# FS-01.net
KiCad netlist of a schematic drawn in Altium Designer
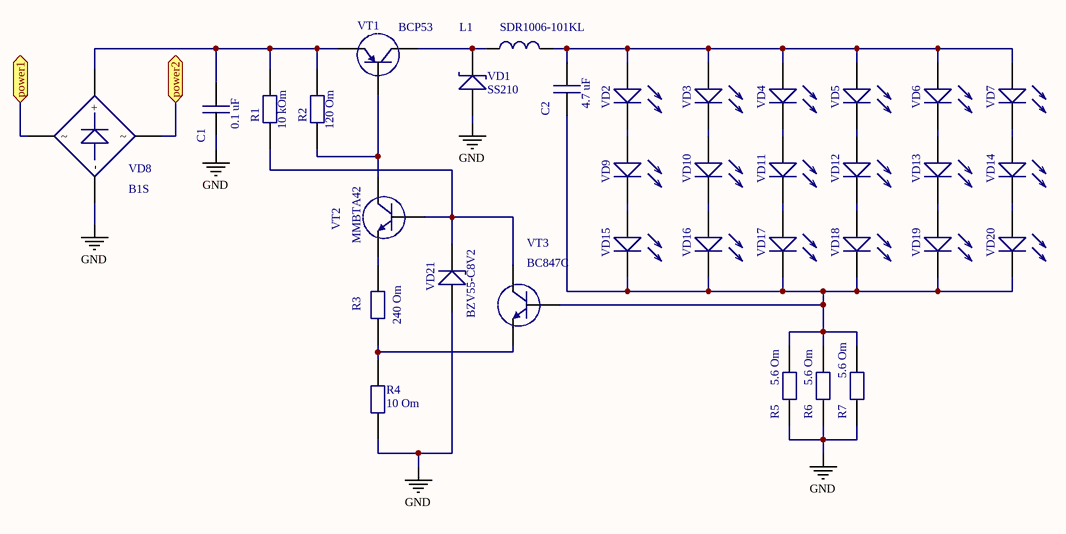
[diagram p0: FS-01.SchDoc]

(export (version "E")
  (design (tool "Eeschema 10.0.6"))
  (components
    (comp (ref "C1")
      (value "0.1 uF")
      (footprint "CAP1206")
      (fields (field (name "Comment") "Capacitor"))
      (libsource (lib "my_library") (part "Capacitor"))
    )
    (comp (ref "C2")
      (value "4.7 uF")
      (footprint "CAP1206")
      (fields (field (name "Comment") "Capacitor"))
      (libsource (lib "my_library") (part "Capacitor"))
    )
    (comp (ref "L1")
      (value "SDR1006-101KL")
      (footprint "SDR1006")
      (fields (field (name "Comment") "coil"))
      (libsource (lib "my_library") (part "coil"))
    )
    (comp (ref "R1")
      (value "10 kOm")
      (footprint "RES1206")
      (fields (field (name "Comment") "Resistor"))
      (libsource (lib "my_library") (part "Resistor"))
    )
    (comp (ref "R2")
      (value "120 Om")
      (footprint "RES1206")
      (fields (field (name "Comment") "Resistor"))
      (libsource (lib "my_library") (part "Resistor"))
    )
    (comp (ref "R3")
      (value "240 Om")
      (footprint "RES1206")
      (fields (field (name "Comment") "Resistor"))
      (libsource (lib "my_library") (part "Resistor"))
    )
    (comp (ref "R4")
      (value "10 Om")
      (footprint "RES1206")
      (fields (field (name "Comment") "Resistor"))
      (libsource (lib "my_library") (part "Resistor"))
    )
    (comp (ref "R5")
      (value "5.6 Om")
      (footprint "RES1206")
      (fields (field (name "Comment") "Resistor"))
      (libsource (lib "my_library") (part "Resistor"))
    )
    (comp (ref "R6")
      (value "5.6 Om")
      (footprint "RES1206")
      (fields (field (name "Comment") "Resistor"))
      (libsource (lib "my_library") (part "Resistor"))
    )
    (comp (ref "R7")
      (value "5.6 Om")
      (footprint "RES1206")
      (fields (field (name "Comment") "Resistor"))
      (libsource (lib "my_library") (part "Resistor"))
    )
    (comp (ref "VD1")
      (value "SS210")
      (footprint "SMB1")
      (fields (field (name "Comment") "Schottky"))
      (libsource (lib "my_library") (part "Schottky"))
    )
    (comp (ref "VD2") (value "LED") (footprint "LED_SAKURA") (libsource (lib "FOS-00 Rev 1_4") (part "LED")))
    (comp (ref "VD3") (value "LED") (footprint "LED_SAKURA") (libsource (lib "FOS-00 Rev 1_4") (part "LED")))
    (comp (ref "VD4") (value "LED") (footprint "LED_SAKURA") (libsource (lib "FOS-00 Rev 1_4") (part "LED")))
    (comp (ref "VD5") (value "LED") (footprint "LED_SAKURA") (libsource (lib "FOS-00 Rev 1_4") (part "LED")))
    (comp (ref "VD6") (value "LED") (footprint "LED_SAKURA") (libsource (lib "FOS-00 Rev 1_4") (part "LED")))
    (comp (ref "VD7") (value "LED") (footprint "LED_SAKURA") (libsource (lib "FOS-00 Rev 1_4") (part "LED")))
    (comp (ref "VD8")
      (value "B1S")
      (footprint "db-1ms")
      (fields (field (name "Comment") "Diode Bridge"))
      (libsource (lib "FOS-00 Rev 1_4") (part "Diode Bridge"))
    )
    (comp (ref "VD9") (value "LED") (footprint "LED_SAKURA") (libsource (lib "FOS-00 Rev 1_4") (part "LED")))
    (comp (ref "VD10") (value "LED") (footprint "LED_SAKURA") (libsource (lib "FOS-00 Rev 1_4") (part "LED")))
    (comp (ref "VD11") (value "LED") (footprint "LED_SAKURA") (libsource (lib "FOS-00 Rev 1_4") (part "LED")))
    (comp (ref "VD12") (value "LED") (footprint "LED_SAKURA") (libsource (lib "FOS-00 Rev 1_4") (part "LED")))
    (comp (ref "VD13") (value "LED") (footprint "LED_SAKURA") (libsource (lib "FOS-00 Rev 1_4") (part "LED")))
    (comp (ref "VD14") (value "LED") (footprint "LED_SAKURA") (libsource (lib "FOS-00 Rev 1_4") (part "LED")))
    (comp (ref "VD15") (value "LED") (footprint "LED_SAKURA") (libsource (lib "FOS-00 Rev 1_4") (part "LED")))
    (comp (ref "VD16") (value "LED") (footprint "LED_SAKURA") (libsource (lib "FOS-00 Rev 1_4") (part "LED")))
    (comp (ref "VD17") (value "LED") (footprint "LED_SAKURA") (libsource (lib "FOS-00 Rev 1_4") (part "LED")))
    (comp (ref "VD18") (value "LED") (footprint "LED_SAKURA") (libsource (lib "FOS-00 Rev 1_4") (part "LED")))
    (comp (ref "VD19") (value "LED") (footprint "LED_SAKURA") (libsource (lib "FOS-00 Rev 1_4") (part "LED")))
    (comp (ref "VD20") (value "LED") (footprint "LED_SAKURA") (libsource (lib "FOS-00 Rev 1_4") (part "LED")))
    (comp (ref "VD21")
      (value "BZV55-C8V2")
      (footprint "minimelf")
      (fields (field (name "Comment") "Zenner"))
      (libsource (lib "my_library") (part "Zenner"))
    )
    (comp (ref "VT1")
      (value "BCP53")
      (footprint "SOT223")
      (fields (field (name "Comment") "PNP"))
      (libsource (lib "my_library") (part "PNP"))
    )
    (comp (ref "VT2")
      (value "MMBTA42")
      (footprint "SOT 23")
      (fields (field (name "Comment") "NPN"))
      (libsource (lib "my_library") (part "NPN"))
    )
    (comp (ref "VT3")
      (value "BC847C")
      (footprint "SOT 23")
      (fields (field (name "Comment") "NPN"))
      (libsource (lib "my_library") (part "NPN"))
    )
  )
  (nets
    (net (code "1") (name "/power1") (class "Default")
      (node (ref "VD8") (pin "3") (pinfunction "~_3") (pintype "passive"))
    )
    (net (code "2") (name "/power2") (class "Default")
      (node (ref "VD8") (pin "4") (pinfunction "~_4") (pintype "passive"))
    )
    (net (code "3") (name "GND") (class "Default")
      (node (ref "C1") (pin "1") (pinfunction "1_1") (pintype "passive"))
      (node (ref "R4") (pin "1") (pinfunction "1_1") (pintype "passive"))
      (node (ref "R5") (pin "1") (pinfunction "1_1") (pintype "passive"))
      (node (ref "R6") (pin "1") (pinfunction "1_1") (pintype "passive"))
      (node (ref "R7") (pin "1") (pinfunction "1_1") (pintype "passive"))
      (node (ref "VD1") (pin "2") (pinfunction "2_2") (pintype "passive"))
      (node (ref "VD21") (pin "2") (pinfunction "2_2") (pintype "passive"))
      (node (ref "VD8") (pin "2") (pinfunction "-_2") (pintype "passive"))
    )
    (net (code "4") (name "Net-(C2-Pad1)") (class "Default")
      (node (ref "C2") (pin "1") (pinfunction "1_1") (pintype "passive"))
      (node (ref "R5") (pin "2") (pinfunction "2_2") (pintype "passive"))
      (node (ref "R6") (pin "2") (pinfunction "2_2") (pintype "passive"))
      (node (ref "R7") (pin "2") (pinfunction "2_2") (pintype "passive"))
      (node (ref "VD15") (pin "1") (pinfunction "1_1") (pintype "passive"))
      (node (ref "VD16") (pin "1") (pinfunction "1_1") (pintype "passive"))
      (node (ref "VD17") (pin "1") (pinfunction "1_1") (pintype "passive"))
      (node (ref "VD18") (pin "1") (pinfunction "1_1") (pintype "passive"))
      (node (ref "VD19") (pin "1") (pinfunction "1_1") (pintype "passive"))
      (node (ref "VD20") (pin "1") (pinfunction "1_1") (pintype "passive"))
      (node (ref "VT3") (pin "B") (pinfunction "B_B") (pintype "passive"))
    )
    (net (code "5") (name "Net-(C2-Pad2)") (class "Default")
      (node (ref "C2") (pin "2") (pinfunction "2_2") (pintype "passive"))
      (node (ref "L1") (pin "2") (pinfunction "2_2") (pintype "passive"))
      (node (ref "VD2") (pin "2") (pinfunction "2_2") (pintype "passive"))
      (node (ref "VD3") (pin "2") (pinfunction "2_2") (pintype "passive"))
      (node (ref "VD4") (pin "2") (pinfunction "2_2") (pintype "passive"))
      (node (ref "VD5") (pin "2") (pinfunction "2_2") (pintype "passive"))
      (node (ref "VD6") (pin "2") (pinfunction "2_2") (pintype "passive"))
      (node (ref "VD7") (pin "2") (pinfunction "2_2") (pintype "passive"))
    )
    (net (code "6") (name "Net-(L1-Pad1)") (class "Default")
      (node (ref "L1") (pin "1") (pinfunction "1_1") (pintype "passive"))
      (node (ref "VD1") (pin "1") (pinfunction "1_1") (pintype "passive"))
      (node (ref "VT1") (pin "K") (pinfunction "K_K") (pintype "passive"))
    )
    (net (code "7") (name "Net-(R1-Pad1)") (class "Default")
      (node (ref "R1") (pin "1") (pinfunction "1_1") (pintype "passive"))
      (node (ref "VD21") (pin "1") (pinfunction "1_1") (pintype "passive"))
      (node (ref "VT2") (pin "B") (pinfunction "B_B") (pintype "passive"))
      (node (ref "VT3") (pin "K") (pinfunction "K_K") (pintype "passive"))
    )
    (net (code "8") (name "Net-(R2-Pad2)") (class "Default")
      (node (ref "R2") (pin "2") (pinfunction "2_2") (pintype "passive"))
      (node (ref "VT1") (pin "B") (pinfunction "B_B") (pintype "passive"))
      (node (ref "VT2") (pin "K") (pinfunction "K_K") (pintype "passive"))
    )
    (net (code "9") (name "Net-(R3-Pad1)") (class "Default")
      (node (ref "R3") (pin "1") (pinfunction "1_1") (pintype "passive"))
      (node (ref "R4") (pin "2") (pinfunction "2_2") (pintype "passive"))
      (node (ref "VT3") (pin "E") (pinfunction "E_E") (pintype "passive"))
    )
    (net (code "10") (name "Net-(R3-Pad2)") (class "Default")
      (node (ref "R3") (pin "2") (pinfunction "2_2") (pintype "passive"))
      (node (ref "VT2") (pin "E") (pinfunction "E_E") (pintype "passive"))
    )
    (net (code "11") (name "Net-(VD2-Pad1)") (class "Default")
      (node (ref "VD2") (pin "1") (pinfunction "1_1") (pintype "passive"))
      (node (ref "VD9") (pin "2") (pinfunction "2_2") (pintype "passive"))
    )
    (net (code "12") (name "Net-(VD8-+)") (class "Default")
      (node (ref "C1") (pin "2") (pinfunction "2_2") (pintype "passive"))
      (node (ref "R1") (pin "2") (pinfunction "2_2") (pintype "passive"))
      (node (ref "R2") (pin "1") (pinfunction "1_1") (pintype "passive"))
      (node (ref "VD8") (pin "1") (pinfunction "+_1") (pintype "passive"))
      (node (ref "VT1") (pin "E") (pinfunction "E_E") (pintype "passive"))
    )
    (net (code "13") (name "Net-(VD10-Pad1)") (class "Default")
      (node (ref "VD10") (pin "1") (pinfunction "1_1") (pintype "passive"))
      (node (ref "VD16") (pin "2") (pinfunction "2_2") (pintype "passive"))
    )
    (net (code "14") (name "Net-(VD10-Pad2)") (class "Default")
      (node (ref "VD10") (pin "2") (pinfunction "2_2") (pintype "passive"))
      (node (ref "VD3") (pin "1") (pinfunction "1_1") (pintype "passive"))
    )
    (net (code "15") (name "Net-(VD11-Pad1)") (class "Default")
      (node (ref "VD11") (pin "1") (pinfunction "1_1") (pintype "passive"))
      (node (ref "VD17") (pin "2") (pinfunction "2_2") (pintype "passive"))
    )
    (net (code "16") (name "Net-(VD11-Pad2)") (class "Default")
      (node (ref "VD11") (pin "2") (pinfunction "2_2") (pintype "passive"))
      (node (ref "VD4") (pin "1") (pinfunction "1_1") (pintype "passive"))
    )
    (net (code "17") (name "Net-(VD12-Pad1)") (class "Default")
      (node (ref "VD12") (pin "1") (pinfunction "1_1") (pintype "passive"))
      (node (ref "VD18") (pin "2") (pinfunction "2_2") (pintype "passive"))
    )
    (net (code "18") (name "Net-(VD12-Pad2)") (class "Default")
      (node (ref "VD12") (pin "2") (pinfunction "2_2") (pintype "passive"))
      (node (ref "VD5") (pin "1") (pinfunction "1_1") (pintype "passive"))
    )
    (net (code "19") (name "Net-(VD13-Pad1)") (class "Default")
      (node (ref "VD13") (pin "1") (pinfunction "1_1") (pintype "passive"))
      (node (ref "VD19") (pin "2") (pinfunction "2_2") (pintype "passive"))
    )
    (net (code "20") (name "Net-(VD13-Pad2)") (class "Default")
      (node (ref "VD13") (pin "2") (pinfunction "2_2") (pintype "passive"))
      (node (ref "VD6") (pin "1") (pinfunction "1_1") (pintype "passive"))
    )
    (net (code "21") (name "Net-(VD14-Pad1)") (class "Default")
      (node (ref "VD14") (pin "1") (pinfunction "1_1") (pintype "passive"))
      (node (ref "VD20") (pin "2") (pinfunction "2_2") (pintype "passive"))
    )
    (net (code "22") (name "Net-(VD14-Pad2)") (class "Default")
      (node (ref "VD14") (pin "2") (pinfunction "2_2") (pintype "passive"))
      (node (ref "VD7") (pin "1") (pinfunction "1_1") (pintype "passive"))
    )
    (net (code "23") (name "Net-(VD15-Pad2)") (class "Default")
      (node (ref "VD15") (pin "2") (pinfunction "2_2") (pintype "passive"))
      (node (ref "VD9") (pin "1") (pinfunction "1_1") (pintype "passive"))
    )
  )
)
